# USB.net
KiCad netlist of a schematic drawn in Altium Designer
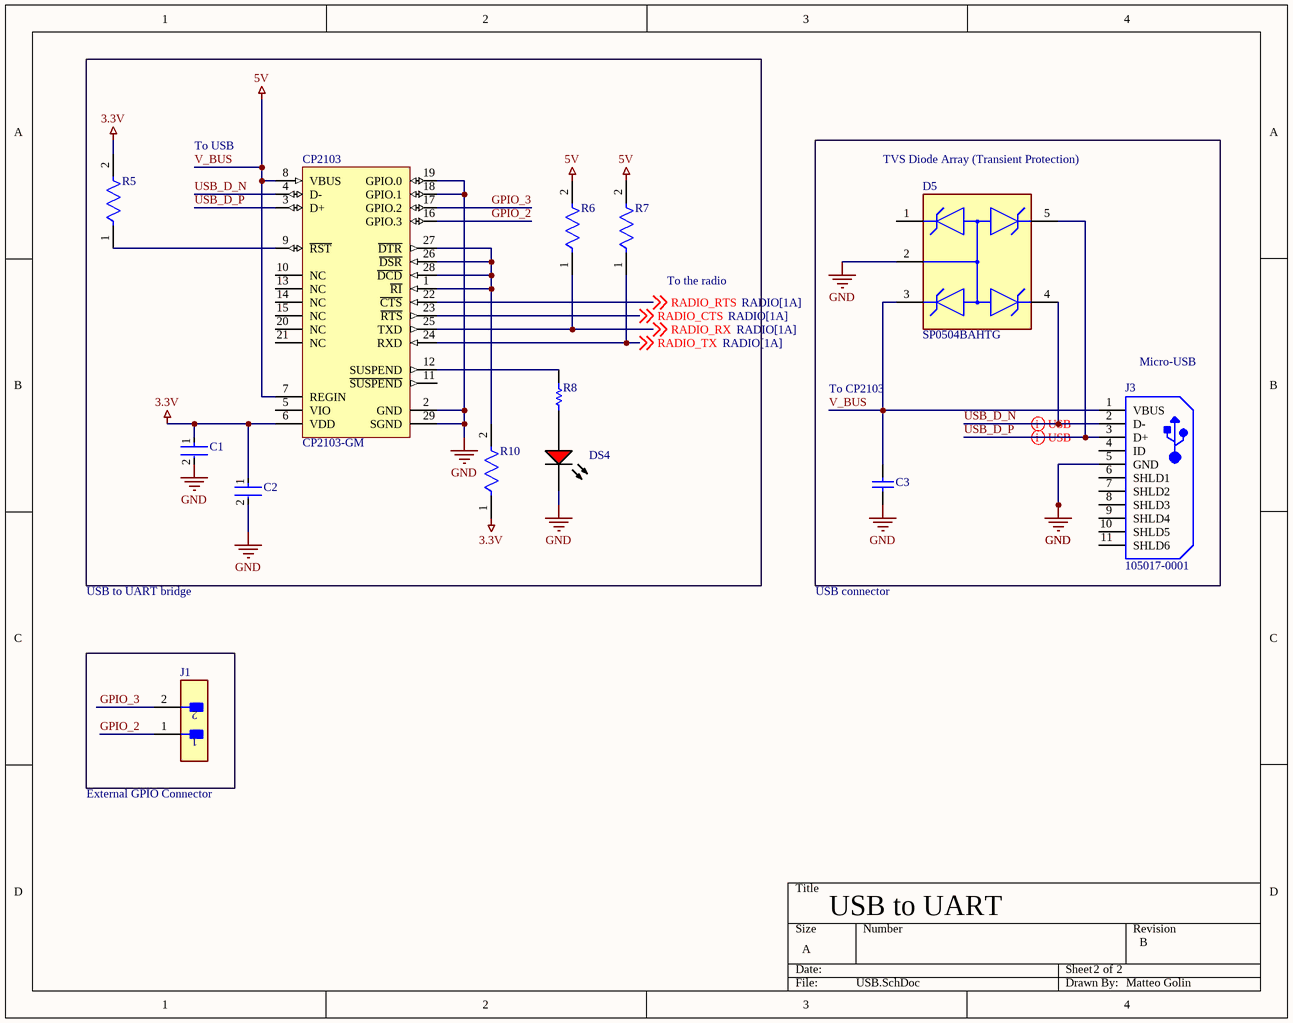
[diagram p0: USB.SchDoc]

(export (version "E")
  (design (tool "Eeschema 10.0.6"))
  (components
    (comp (ref "C1")
      (value "C0603C104K5RACTU")
      (footprint "FP-C0603C-CF-MFG")
      (description "CAP CER 0.1UF 50V X7R 0603")
      (fields (field (name "TOLERANCE") "0.1") (field (name "MANUFACTURER") "KEMET"))
      (libsource (lib "Altium Content Vault") (part "b4654b650e69147ec39a6b967a45e02"))
    )
    (comp (ref "C2")
      (value "C0603C475K9PACTU")
      (footprint "FP-C0603-CG-MFG")
      (description "CAP CER 4.7UF 6.3V X5R 0603")
      (fields (field (name "TOLERANCE") "10%") (field (name "MANUFACTURER") "Kemet"))
      (libsource (lib "Altium Content Vault") (part "11868f565c42a9108669ba33697ecf6"))
    )
    (comp (ref "C3")
      (value "C1206C105K5RACTU")
      (footprint "CAPC3216X110X50LL20T25")
      (description "Chip Capacitor, 1 uF, +/- 10%, 50 V, -55 to 125 degC, 1206 (3216 Metric), RoHS, Tape and Reel")
      (fields (field (name "MANUFACTURER") "Kemet") (field (name "TOLERANCE") "10%"))
      (libsource (lib "Altium Content Vault") (part "CAP-NP-2"))
    )
    (comp (ref "CP2103")
      (value "CP2103-GM")
      (footprint "SLAB-QFN-28-3125x3125TP_A_M")
      (description "Single-Chip USB to UART Bridge, 1024 Bytes EEPROM, -40 to 85 degC, 28-pin QFN, Tube")
      (fields (field (name "MANUFACTURER") "Silicon Labs"))
      (libsource (lib "Altium Content Vault") (part "SLAB-CP2103-QFN-28-29"))
    )
    (comp (ref "D5")
      (value "SP0504BAHTG")
      (footprint "FP-SP0504BAHTG-MFG")
      (description "TVS DIODE 5.5V 8.5V SOT23-5")
      (fields
        (field (name "OCTOPART") "https://octopart.com/sp0504bahtg-littelfuse-587259")
        (field (name "MANUFACTURER") "Littelfuse")
      )
      (libsource (lib "Altium Content Vault") (part "766daeda9d65f3a5afe6095573230ef"))
    )
    (comp (ref "DS4")
      (value "HSMH-C190")
      (footprint "AVAG-HSMX-C190_V")
      (description "LED Uni-Color Red, 65 mW, 20 mA, -40 to 85 degC, 2-Pin SMD, RoHS, Tape and Reel")
      (libsource (lib "Altium Content Vault") (part "LED-RED-AK-2"))
    )
    (comp (ref "J1")
      (value "M22-2510205")
      (footprint "FP-M22-2510205-MFG")
      (description "CONN HEADER VERT 2POS 2MM")
      (fields
        (field (name "MANUFACTURER") "Harwin")
        (field (name "OCTOPART") "https://octopart.com/m22-2510205-harwin-2538221")
      )
      (libsource (lib "Altium Content Vault") (part "3bc925449376181038e59eaffc5286c"))
    )
    (comp (ref "J3")
      (value "105017-0001")
      (footprint "USB-MICRO-B_V")
      (fields (field (name "MANUFACTURER") "Molex"))
      (libsource (lib "Altium Content Vault") (part "USB-5-6SHLD"))
    )
    (comp (ref "R5")
      (value "CRCW040210K0FKED")
      (footprint "FP-CRCW0402-e3-IPC_B")
      (description "RES SMD 10K OHM 1% 1/16W 0402")
      (fields (field (name "TOLERANCE") "1%"))
      (libsource (lib "Altium Content Vault") (part "1029c3af85768c4190bb7ad29bc67b5"))
    )
    (comp (ref "R6")
      (value "CRCW0402100KFKED")
      (footprint "FP-CRCW0402-e3-IPC_C")
      (description "RES Thick Film, 100kΩ, 1%, 0.063W, 100ppm/°C, 0402")
      (fields (field (name "TOLERANCE") "1%"))
      (libsource (lib "Altium Content Vault") (part "1029c3af85768c4190bb7ad29bc67b5"))
    )
    (comp (ref "R7")
      (value "CRCW0402100KFKED")
      (footprint "FP-CRCW0402-e3-IPC_C")
      (description "RES Thick Film, 100kΩ, 1%, 0.063W, 100ppm/°C, 0402")
      (fields (field (name "TOLERANCE") "1%"))
      (libsource (lib "Altium Content Vault") (part "1029c3af85768c4190bb7ad29bc67b5"))
    )
    (comp (ref "R8")
      (value "CRCW0402220KFKED")
      (footprint "RESC1005X40X25LL05T05")
      (fields (field (name "MANUFACTURER") "Vishay Dale"))
      (libsource (lib "Altium Content Vault") (part "RES"))
    )
    (comp (ref "R10")
      (value "CRCW040210K0FKED")
      (footprint "FP-CRCW0402-e3-IPC_B")
      (description "RES SMD 10K OHM 1% 1/16W 0402")
      (fields (field (name "TOLERANCE") "1%"))
      (libsource (lib "Altium Content Vault") (part "1029c3af85768c4190bb7ad29bc67b5"))
    )
  )
  (nets
    (net (code "1") (name "/GPIO_2") (class "Default")
      (node (ref "CP2103") (pin "16") (pinfunction "GPIO.3_16") (pintype "bidirectional"))
      (node (ref "J1") (pin "1") (pinfunction "1_1") (pintype "passive"))
    )
    (net (code "2") (name "/GPIO_3") (class "Default")
      (node (ref "CP2103") (pin "17") (pinfunction "GPIO.2_17") (pintype "bidirectional"))
      (node (ref "J1") (pin "2") (pinfunction "2_2") (pintype "passive"))
    )
    (net (code "3") (name "/USB_D_N") (class "Default")
      (node (ref "CP2103") (pin "4") (pinfunction "D-_4") (pintype "bidirectional"))
      (node (ref "D5") (pin "4") (pinfunction "4_4") (pintype "passive"))
      (node (ref "J3") (pin "2") (pinfunction "D-_2") (pintype "passive"))
    )
    (net (code "4") (name "/USB_D_P") (class "Default")
      (node (ref "CP2103") (pin "3") (pinfunction "D+_3") (pintype "bidirectional"))
      (node (ref "D5") (pin "5") (pinfunction "5_5") (pintype "passive"))
      (node (ref "J3") (pin "3") (pinfunction "D+_3") (pintype "passive"))
    )
    (net (code "5") (name "3.3V") (class "Default")
      (node (ref "C1") (pin "1") (pinfunction "1_1") (pintype "passive"))
      (node (ref "C2") (pin "1") (pinfunction "1_1") (pintype "passive"))
      (node (ref "CP2103") (pin "6") (pinfunction "VDD_6") (pintype "power_in"))
      (node (ref "R10") (pin "1") (pinfunction "1_1") (pintype "passive"))
      (node (ref "R5") (pin "2") (pinfunction "2_2") (pintype "passive"))
    )
    (net (code "6") (name "5V") (class "Default")
      (node (ref "C3") (pin "2") (pinfunction "2_2") (pintype "passive"))
      (node (ref "CP2103") (pin "7") (pinfunction "REGIN_7") (pintype "power_in"))
      (node (ref "CP2103") (pin "8") (pinfunction "VBUS_8") (pintype "input"))
      (node (ref "D5") (pin "3") (pinfunction "3_3") (pintype "passive"))
      (node (ref "J3") (pin "1") (pinfunction "VBUS_1") (pintype "passive"))
      (node (ref "R6") (pin "2") (pinfunction "2_2") (pintype "passive"))
      (node (ref "R7") (pin "2") (pinfunction "2_2") (pintype "passive"))
    )
    (net (code "7") (name "GND") (class "Default")
      (node (ref "C1") (pin "2") (pinfunction "2_2") (pintype "passive"))
      (node (ref "C2") (pin "2") (pinfunction "2_2") (pintype "passive"))
      (node (ref "C3") (pin "1") (pinfunction "1_1") (pintype "passive"))
      (node (ref "CP2103") (pin "18") (pinfunction "GPIO.1_18") (pintype "bidirectional"))
      (node (ref "CP2103") (pin "19") (pinfunction "GPIO.0_19") (pintype "bidirectional"))
      (node (ref "CP2103") (pin "2") (pinfunction "GND_2") (pintype "power_in"))
      (node (ref "CP2103") (pin "29") (pinfunction "SGND_29") (pintype "power_in"))
      (node (ref "D5") (pin "2") (pinfunction "2_2") (pintype "passive"))
      (node (ref "DS4") (pin "2") (pinfunction "K_2") (pintype "passive"))
      (node (ref "J3") (pin "5") (pinfunction "GND_5") (pintype "passive"))
    )
    (net (code "8") (name "Net-(CP2103-SUSPEND)") (class "Default")
      (node (ref "CP2103") (pin "12") (pinfunction "SUSPEND_12") (pintype "output"))
      (node (ref "R8") (pin "2") (pinfunction "2_2") (pintype "passive"))
    )
    (net (code "9") (name "Net-(CP2103-~{DCD})") (class "Default")
      (node (ref "CP2103") (pin "1") (pinfunction "~{RI}_1") (pintype "input"))
      (node (ref "CP2103") (pin "26") (pinfunction "~{DSR}_26") (pintype "input"))
      (node (ref "CP2103") (pin "27") (pinfunction "~{DTR}_27") (pintype "output"))
      (node (ref "CP2103") (pin "28") (pinfunction "~{DCD}_28") (pintype "input"))
      (node (ref "R10") (pin "2") (pinfunction "2_2") (pintype "passive"))
    )
    (net (code "10") (name "Net-(CP2103-~{RST})") (class "Default")
      (node (ref "CP2103") (pin "9") (pinfunction "~{RST}_9") (pintype "bidirectional"))
      (node (ref "R5") (pin "1") (pinfunction "1_1") (pintype "passive"))
    )
    (net (code "11") (name "Net-(DS4-A)") (class "Default")
      (node (ref "DS4") (pin "1") (pinfunction "A_1") (pintype "passive"))
      (node (ref "R8") (pin "1") (pinfunction "1_1") (pintype "passive"))
    )
    (net (code "12") (name "RADIO_CTS") (class "Default")
      (node (ref "CP2103") (pin "23") (pinfunction "~{RTS}_23") (pintype "output"))
    )
    (net (code "13") (name "RADIO_RTS") (class "Default")
      (node (ref "CP2103") (pin "22") (pinfunction "~{CTS}_22") (pintype "input"))
    )
    (net (code "14") (name "RADIO_RX") (class "Default")
      (node (ref "CP2103") (pin "25") (pinfunction "TXD_25") (pintype "output"))
      (node (ref "R6") (pin "1") (pinfunction "1_1") (pintype "passive"))
    )
    (net (code "15") (name "RADIO_TX") (class "Default")
      (node (ref "CP2103") (pin "24") (pinfunction "RXD_24") (pintype "input"))
      (node (ref "R7") (pin "1") (pinfunction "1_1") (pintype "passive"))
    )
    (net (code "16") (name "unconnected-(CP2103-NC-Pad10)") (class "Default")
      (node (ref "CP2103") (pin "10") (pinfunction "NC_10") (pintype "passive"))
    )
    (net (code "17") (name "unconnected-(CP2103-NC-Pad13)") (class "Default")
      (node (ref "CP2103") (pin "13") (pinfunction "NC_13") (pintype "passive"))
    )
    (net (code "18") (name "unconnected-(CP2103-NC-Pad14)") (class "Default")
      (node (ref "CP2103") (pin "14") (pinfunction "NC_14") (pintype "passive"))
    )
    (net (code "19") (name "unconnected-(CP2103-NC-Pad15)") (class "Default")
      (node (ref "CP2103") (pin "15") (pinfunction "NC_15") (pintype "passive"))
    )
    (net (code "20") (name "unconnected-(CP2103-NC-Pad20)") (class "Default")
      (node (ref "CP2103") (pin "20") (pinfunction "NC_20") (pintype "passive"))
    )
    (net (code "21") (name "unconnected-(CP2103-NC-Pad21)") (class "Default")
      (node (ref "CP2103") (pin "21") (pinfunction "NC_21") (pintype "passive"))
    )
    (net (code "22") (name "unconnected-(CP2103-VIO-Pad5)") (class "Default")
      (node (ref "CP2103") (pin "5") (pinfunction "VIO_5") (pintype "power_in"))
    )
    (net (code "23") (name "unconnected-(CP2103-~{SUSPEND}-Pad11)") (class "Default")
      (node (ref "CP2103") (pin "11") (pinfunction "~{SUSPEND}_11") (pintype "output"))
    )
    (net (code "24") (name "unconnected-(D5-Pad1)") (class "Default")
      (node (ref "D5") (pin "1") (pinfunction "1_1") (pintype "passive"))
    )
    (net (code "25") (name "unconnected-(J3-ID-Pad4)") (class "Default")
      (node (ref "J3") (pin "4") (pinfunction "ID_4") (pintype "passive"))
    )
    (net (code "26") (name "unconnected-(J3-SHLD1-Pad6)") (class "Default")
      (node (ref "J3") (pin "6") (pinfunction "SHLD1_6") (pintype "passive"))
    )
    (net (code "27") (name "unconnected-(J3-SHLD2-Pad7)") (class "Default")
      (node (ref "J3") (pin "7") (pinfunction "SHLD2_7") (pintype "passive"))
    )
    (net (code "28") (name "unconnected-(J3-SHLD3-Pad8)") (class "Default")
      (node (ref "J3") (pin "8") (pinfunction "SHLD3_8") (pintype "passive"))
    )
    (net (code "29") (name "unconnected-(J3-SHLD4-Pad9)") (class "Default")
      (node (ref "J3") (pin "9") (pinfunction "SHLD4_9") (pintype "passive"))
    )
    (net (code "30") (name "unconnected-(J3-SHLD5-Pad10)") (class "Default")
      (node (ref "J3") (pin "10") (pinfunction "SHLD5_10") (pintype "passive"))
    )
    (net (code "31") (name "unconnected-(J3-SHLD6-Pad11)") (class "Default")
      (node (ref "J3") (pin "11") (pinfunction "SHLD6_11") (pintype "passive"))
    )
  )
)
